# STM32.net
KiCad netlist of a schematic drawn in Altium Designer
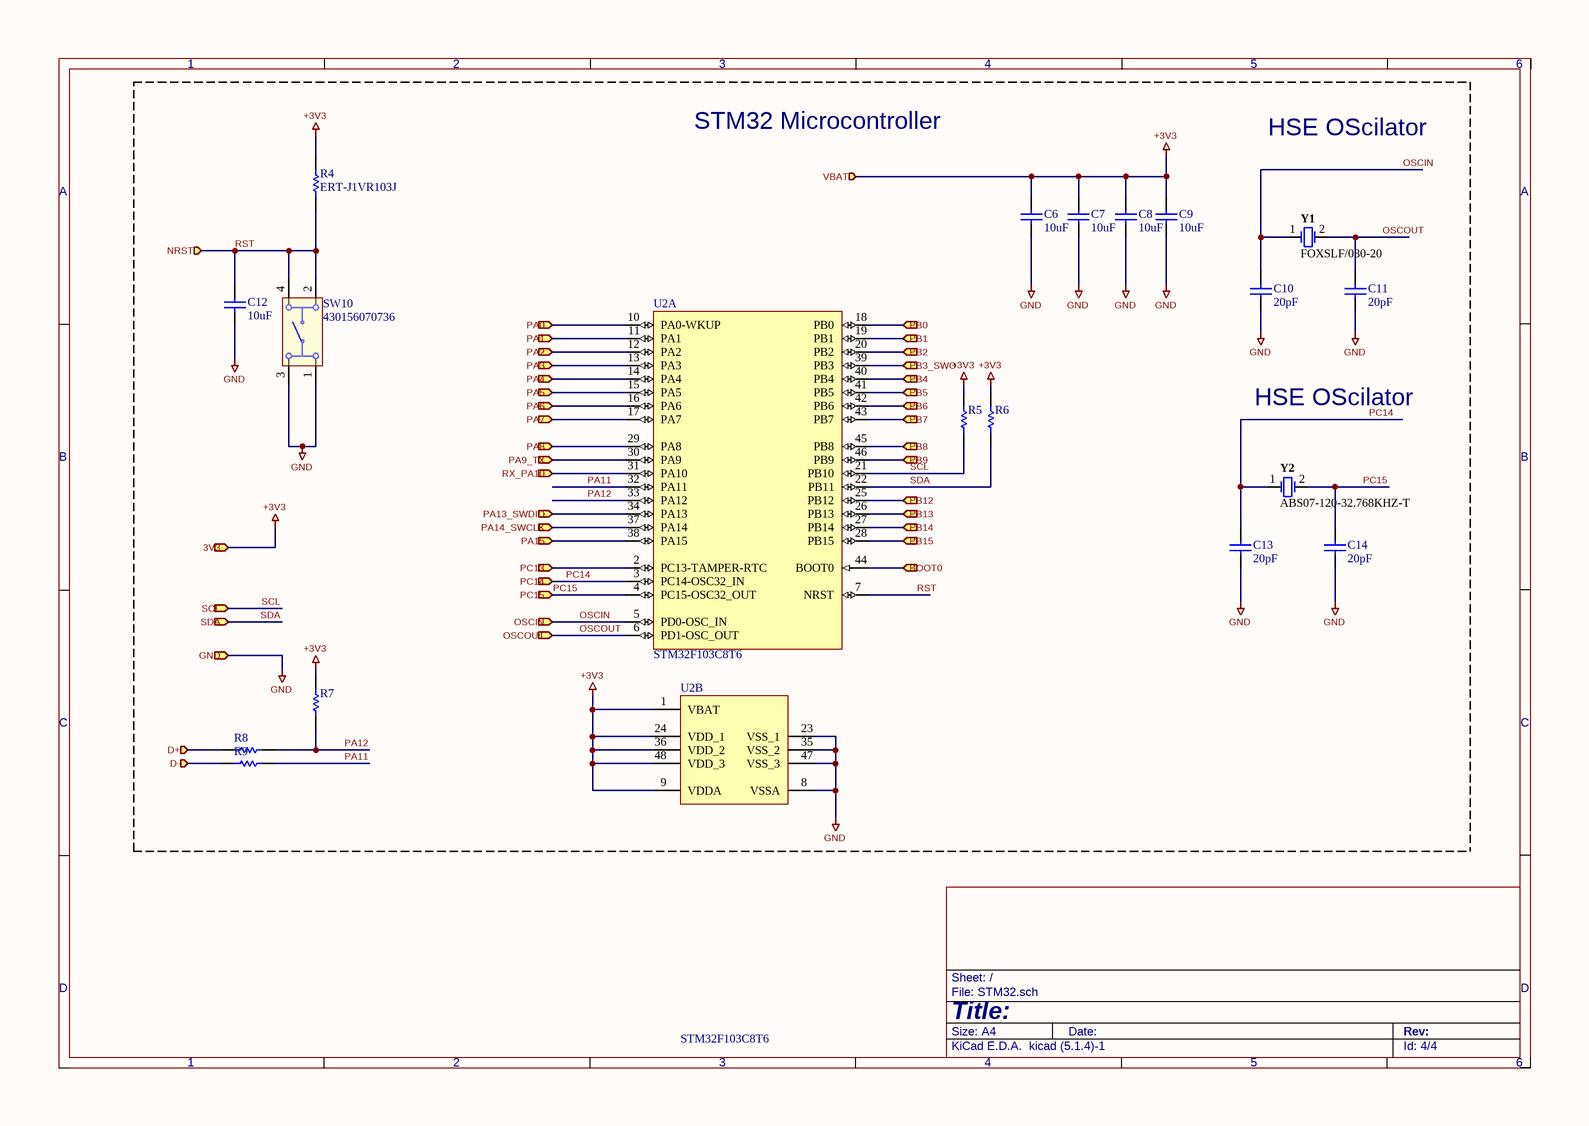
[diagram p0: STM32.SchDoc]

(export (version "E")
  (design (tool "Eeschema 10.0.6"))
  (components
    (comp (ref "C6")
      (value "10uF")
      (footprint "CAPC1608X90X35NL10T15")
      (fields (field (name "PART NUMBER") "GRM188R60J106ME47D") (field (name "MANUFACTURER") "Murata"))
      (libsource (lib "Altium Content Vault") (part "CAP"))
    )
    (comp (ref "C7")
      (value "10uF")
      (footprint "CAPC1608X90X35NL10T15")
      (fields (field (name "PART NUMBER") "GRM188R60J106ME47D") (field (name "MANUFACTURER") "Murata"))
      (libsource (lib "Altium Content Vault") (part "CAP"))
    )
    (comp (ref "C8")
      (value "10uF")
      (footprint "CAPC1608X90X35NL10T15")
      (fields (field (name "PART NUMBER") "GRM188R60J106ME47D") (field (name "MANUFACTURER") "Murata"))
      (libsource (lib "Altium Content Vault") (part "CAP"))
    )
    (comp (ref "C9")
      (value "10uF")
      (footprint "CAPC1608X90X35NL10T15")
      (fields (field (name "PART NUMBER") "GRM188R60J106ME47D") (field (name "MANUFACTURER") "Murata"))
      (libsource (lib "Altium Content Vault") (part "CAP"))
    )
    (comp (ref "C10")
      (value "20pF")
      (footprint "CAPC1608X90X35NL10T15")
      (fields (field (name "PART NUMBER") "GRM188R60J106ME47D") (field (name "MANUFACTURER") "Murata"))
      (libsource (lib "Altium Content Vault") (part "CAP"))
    )
    (comp (ref "C11")
      (value "20pF")
      (footprint "CAPC1608X90X35NL10T15")
      (fields (field (name "PART NUMBER") "GRM188R60J106ME47D") (field (name "MANUFACTURER") "Murata"))
      (libsource (lib "Altium Content Vault") (part "CAP"))
    )
    (comp (ref "C12")
      (value "10uF")
      (footprint "CAPC1608X90X35NL10T15")
      (fields (field (name "PART NUMBER") "GRM188R60J106ME47D") (field (name "MANUFACTURER") "Murata"))
      (libsource (lib "Altium Content Vault") (part "CAP"))
    )
    (comp (ref "C13")
      (value "20pF")
      (footprint "CAPC1608X90X35NL10T15")
      (fields (field (name "PART NUMBER") "GRM188R60J106ME47D") (field (name "MANUFACTURER") "Murata"))
      (libsource (lib "Altium Content Vault") (part "CAP"))
    )
    (comp (ref "C14")
      (value "20pF")
      (footprint "CAPC1608X90X35NL10T15")
      (fields (field (name "PART NUMBER") "GRM188R60J106ME47D") (field (name "MANUFACTURER") "Murata"))
      (libsource (lib "Altium Content Vault") (part "CAP"))
    )
    (comp (ref "R4")
      (value "ERT-J1VR103J")
      (footprint "RESC1608X90X30LL15T20")
      (fields (field (name "MANUFACTURER") "Panasonic"))
      (libsource (lib "Altium Content Vault") (part "RES"))
    )
    (comp (ref "R5")
      (value "ERT-J1VR103J")
      (footprint "RESC1608X90X30LL15T20")
      (fields (field (name "MANUFACTURER") "Panasonic"))
      (libsource (lib "Altium Content Vault") (part "RES"))
    )
    (comp (ref "R6")
      (value "ERT-J1VR103J")
      (footprint "RESC1608X90X30LL15T20")
      (fields (field (name "MANUFACTURER") "Panasonic"))
      (libsource (lib "Altium Content Vault") (part "RES"))
    )
    (comp (ref "R7")
      (value "ERT-J1VR103J")
      (footprint "RESC1608X90X30LL15T20")
      (fields (field (name "MANUFACTURER") "Panasonic"))
      (libsource (lib "Altium Content Vault") (part "RES"))
    )
    (comp (ref "R8")
      (value "ERT-J1VR103J")
      (footprint "RESC1608X90X30LL15T20")
      (fields (field (name "MANUFACTURER") "Panasonic"))
      (libsource (lib "Altium Content Vault") (part "RES"))
    )
    (comp (ref "R9")
      (value "ERT-J1VR103J")
      (footprint "RESC1608X90X30LL15T20")
      (fields (field (name "MANUFACTURER") "Panasonic"))
      (libsource (lib "Altium Content Vault") (part "RES"))
    )
    (comp (ref "SW10")
      (value "430156070736")
      (footprint "430156070736")
      (description "WS-TATV THT Tact Switch 6X6 mm")
      (fields (field (name "MANUFACTURER") "Wuerth Elektronik"))
      (libsource (lib "Altium Content Vault") (part "WE-TACT-SW-4"))
    )
    (comp (ref "U2")
      (value "STM32F103C8T6")
      (footprint "STM-LQFP48_L")
      (libsource (lib "Altium Content Vault") (part "MC-ARM-STM32F103X8_B-SQ48"))
    )
    (comp (ref "Y1")
      (value "FOXSLF/080-20")
      (footprint "FOX-FOXSLF080-20")
      (description "Resistance Weld Thru-Hole Crystal, 8 MHz, -20 to 70 degC, 2-Pin THD, RoHS, Bulk")
      (libsource (lib "Altium Content Vault") (part "XTAL-1-2-2"))
    )
    (comp (ref "Y2")
      (value "ABS07-120-32.768KHZ-T")
      (footprint "ABRA-ABS07_A_V")
      (description "Tuning Fork Crystal, 32.768 KHz, +/- 20 ppm, -40 to 85 degC, 2-Pin SMD, RoHS, Tape and Reel")
      (fields (field (name "MANUFACTURER") "Abracon") (field (name "TOLERANCE") "20ppm"))
      (libsource (lib "Altium Content Vault") (part "XTAL-1-2-2"))
    )
  )
  (nets
    (net (code "1") (name "+3V3") (class "Default")
      (node (ref "C6") (pin "2") (pinfunction "2_2") (pintype "passive"))
      (node (ref "C7") (pin "2") (pinfunction "2_2") (pintype "passive"))
      (node (ref "C8") (pin "2") (pinfunction "2_2") (pintype "passive"))
      (node (ref "C9") (pin "2") (pinfunction "2_2") (pintype "passive"))
      (node (ref "R4") (pin "2") (pinfunction "2_2") (pintype "passive"))
      (node (ref "R5") (pin "2") (pinfunction "2_2") (pintype "passive"))
      (node (ref "R6") (pin "2") (pinfunction "2_2") (pintype "passive"))
      (node (ref "R7") (pin "2") (pinfunction "2_2") (pintype "passive"))
      (node (ref "U2") (pin "1") (pinfunction "VBAT_1") (pintype "power_in"))
      (node (ref "U2") (pin "24") (pinfunction "VDD_1_24") (pintype "power_in"))
      (node (ref "U2") (pin "36") (pinfunction "VDD_2_36") (pintype "power_in"))
      (node (ref "U2") (pin "48") (pinfunction "VDD_3_48") (pintype "power_in"))
      (node (ref "U2") (pin "9") (pinfunction "VDDA_9") (pintype "power_in"))
    )
    (net (code "2") (name "/BOOT0") (class "Default")
      (node (ref "U2") (pin "44") (pinfunction "BOOT0_44") (pintype "input"))
    )
    (net (code "3") (name "/D+") (class "Default")
      (node (ref "R8") (pin "2") (pinfunction "2_2") (pintype "passive"))
    )
    (net (code "4") (name "/D-") (class "Default")
      (node (ref "R9") (pin "2") (pinfunction "2_2") (pintype "passive"))
    )
    (net (code "5") (name "/OSCIN") (class "Default")
      (node (ref "C10") (pin "2") (pinfunction "2_2") (pintype "passive"))
      (node (ref "U2") (pin "5") (pinfunction "PD0-OSC_IN_5") (pintype "bidirectional"))
      (node (ref "Y1") (pin "1") (pinfunction "1_1") (pintype "passive"))
    )
    (net (code "6") (name "/OSCOUT") (class "Default")
      (node (ref "C11") (pin "2") (pinfunction "2_2") (pintype "passive"))
      (node (ref "U2") (pin "6") (pinfunction "PD1-OSC_OUT_6") (pintype "bidirectional"))
      (node (ref "Y1") (pin "2") (pinfunction "2_2") (pintype "passive"))
    )
    (net (code "7") (name "/PA0") (class "Default")
      (node (ref "U2") (pin "10") (pinfunction "PA0-WKUP_10") (pintype "bidirectional"))
    )
    (net (code "8") (name "/PA1") (class "Default")
      (node (ref "U2") (pin "11") (pinfunction "PA1_11") (pintype "bidirectional"))
    )
    (net (code "9") (name "/PA2") (class "Default")
      (node (ref "U2") (pin "12") (pinfunction "PA2_12") (pintype "bidirectional"))
    )
    (net (code "10") (name "/PA3") (class "Default")
      (node (ref "U2") (pin "13") (pinfunction "PA3_13") (pintype "bidirectional"))
    )
    (net (code "11") (name "/PA4") (class "Default")
      (node (ref "U2") (pin "14") (pinfunction "PA4_14") (pintype "bidirectional"))
    )
    (net (code "12") (name "/PA5") (class "Default")
      (node (ref "U2") (pin "15") (pinfunction "PA5_15") (pintype "bidirectional"))
    )
    (net (code "13") (name "/PA6") (class "Default")
      (node (ref "U2") (pin "16") (pinfunction "PA6_16") (pintype "bidirectional"))
    )
    (net (code "14") (name "/PA7") (class "Default")
      (node (ref "U2") (pin "17") (pinfunction "PA7_17") (pintype "bidirectional"))
    )
    (net (code "15") (name "/PA8") (class "Default")
      (node (ref "U2") (pin "29") (pinfunction "PA8_29") (pintype "bidirectional"))
    )
    (net (code "16") (name "/PA9_TX") (class "Default")
      (node (ref "U2") (pin "30") (pinfunction "PA9_30") (pintype "bidirectional"))
    )
    (net (code "17") (name "/PA11") (class "Default")
      (node (ref "R9") (pin "1") (pinfunction "1_1") (pintype "passive"))
      (node (ref "U2") (pin "32") (pinfunction "PA11_32") (pintype "bidirectional"))
    )
    (net (code "18") (name "/PA12") (class "Default")
      (node (ref "R7") (pin "1") (pinfunction "1_1") (pintype "passive"))
      (node (ref "R8") (pin "1") (pinfunction "1_1") (pintype "passive"))
      (node (ref "U2") (pin "33") (pinfunction "PA12_33") (pintype "bidirectional"))
    )
    (net (code "19") (name "/PA13_SWDIO") (class "Default")
      (node (ref "U2") (pin "34") (pinfunction "PA13_34") (pintype "bidirectional"))
    )
    (net (code "20") (name "/PA14_SWCLK") (class "Default")
      (node (ref "U2") (pin "37") (pinfunction "PA14_37") (pintype "bidirectional"))
    )
    (net (code "21") (name "/PA15") (class "Default")
      (node (ref "U2") (pin "38") (pinfunction "PA15_38") (pintype "bidirectional"))
    )
    (net (code "22") (name "/PB0") (class "Default")
      (node (ref "U2") (pin "18") (pinfunction "PB0_18") (pintype "bidirectional"))
    )
    (net (code "23") (name "/PB1") (class "Default")
      (node (ref "U2") (pin "19") (pinfunction "PB1_19") (pintype "bidirectional"))
    )
    (net (code "24") (name "/PB2") (class "Default")
      (node (ref "U2") (pin "20") (pinfunction "PB2_20") (pintype "bidirectional"))
    )
    (net (code "25") (name "/PB3_SWO") (class "Default")
      (node (ref "U2") (pin "39") (pinfunction "PB3_39") (pintype "bidirectional"))
    )
    (net (code "26") (name "/PB4") (class "Default")
      (node (ref "U2") (pin "40") (pinfunction "PB4_40") (pintype "bidirectional"))
    )
    (net (code "27") (name "/PB5") (class "Default")
      (node (ref "U2") (pin "41") (pinfunction "PB5_41") (pintype "bidirectional"))
    )
    (net (code "28") (name "/PB6") (class "Default")
      (node (ref "U2") (pin "42") (pinfunction "PB6_42") (pintype "bidirectional"))
    )
    (net (code "29") (name "/PB7") (class "Default")
      (node (ref "U2") (pin "43") (pinfunction "PB7_43") (pintype "bidirectional"))
    )
    (net (code "30") (name "/PB8") (class "Default")
      (node (ref "U2") (pin "45") (pinfunction "PB8_45") (pintype "bidirectional"))
    )
    (net (code "31") (name "/PB9") (class "Default")
      (node (ref "U2") (pin "46") (pinfunction "PB9_46") (pintype "bidirectional"))
    )
    (net (code "32") (name "/PB12") (class "Default")
      (node (ref "U2") (pin "25") (pinfunction "PB12_25") (pintype "bidirectional"))
    )
    (net (code "33") (name "/PB13") (class "Default")
      (node (ref "U2") (pin "26") (pinfunction "PB13_26") (pintype "bidirectional"))
    )
    (net (code "34") (name "/PB14") (class "Default")
      (node (ref "U2") (pin "27") (pinfunction "PB14_27") (pintype "bidirectional"))
    )
    (net (code "35") (name "/PB15") (class "Default")
      (node (ref "U2") (pin "28") (pinfunction "PB15_28") (pintype "bidirectional"))
    )
    (net (code "36") (name "/PC13") (class "Default")
      (node (ref "U2") (pin "2") (pinfunction "PC13-TAMPER-RTC_2") (pintype "bidirectional"))
    )
    (net (code "37") (name "/PC14") (class "Default")
      (node (ref "C13") (pin "2") (pinfunction "2_2") (pintype "passive"))
      (node (ref "U2") (pin "3") (pinfunction "PC14-OSC32_IN_3") (pintype "bidirectional"))
      (node (ref "Y2") (pin "1") (pinfunction "1_1") (pintype "passive"))
    )
    (net (code "38") (name "/PC15") (class "Default")
      (node (ref "C14") (pin "2") (pinfunction "2_2") (pintype "passive"))
      (node (ref "U2") (pin "4") (pinfunction "PC15-OSC32_OUT_4") (pintype "bidirectional"))
      (node (ref "Y2") (pin "2") (pinfunction "2_2") (pintype "passive"))
    )
    (net (code "39") (name "/RST") (class "Default")
      (node (ref "C12") (pin "2") (pinfunction "2_2") (pintype "passive"))
      (node (ref "R4") (pin "1") (pinfunction "1_1") (pintype "passive"))
      (node (ref "SW10") (pin "2") (pinfunction "2_2") (pintype "passive"))
      (node (ref "SW10") (pin "4") (pinfunction "4_4") (pintype "passive"))
      (node (ref "U2") (pin "7") (pinfunction "NRST_7") (pintype "bidirectional"))
    )
    (net (code "40") (name "/RX_PA10") (class "Default")
      (node (ref "U2") (pin "31") (pinfunction "PA10_31") (pintype "bidirectional"))
    )
    (net (code "41") (name "/SCL") (class "Default")
      (node (ref "R5") (pin "1") (pinfunction "1_1") (pintype "passive"))
      (node (ref "U2") (pin "21") (pinfunction "PB10_21") (pintype "bidirectional"))
    )
    (net (code "42") (name "/SDA") (class "Default")
      (node (ref "R6") (pin "1") (pinfunction "1_1") (pintype "passive"))
      (node (ref "U2") (pin "22") (pinfunction "PB11_22") (pintype "bidirectional"))
    )
    (net (code "43") (name "GND") (class "Default")
      (node (ref "C10") (pin "1") (pinfunction "1_1") (pintype "passive"))
      (node (ref "C11") (pin "1") (pinfunction "1_1") (pintype "passive"))
      (node (ref "C12") (pin "1") (pinfunction "1_1") (pintype "passive"))
      (node (ref "C13") (pin "1") (pinfunction "1_1") (pintype "passive"))
      (node (ref "C14") (pin "1") (pinfunction "1_1") (pintype "passive"))
      (node (ref "C6") (pin "1") (pinfunction "1_1") (pintype "passive"))
      (node (ref "C7") (pin "1") (pinfunction "1_1") (pintype "passive"))
      (node (ref "C8") (pin "1") (pinfunction "1_1") (pintype "passive"))
      (node (ref "C9") (pin "1") (pinfunction "1_1") (pintype "passive"))
      (node (ref "SW10") (pin "1") (pinfunction "1_1") (pintype "passive"))
      (node (ref "SW10") (pin "3") (pinfunction "3_3") (pintype "passive"))
      (node (ref "U2") (pin "23") (pinfunction "VSS_1_23") (pintype "power_in"))
      (node (ref "U2") (pin "35") (pinfunction "VSS_2_35") (pintype "power_in"))
      (node (ref "U2") (pin "47") (pinfunction "VSS_3_47") (pintype "power_in"))
      (node (ref "U2") (pin "8") (pinfunction "VSSA_8") (pintype "power_in"))
    )
  )
)
